# ETH_IFC.net
KiCad netlist of a schematic drawn in Altium Designer
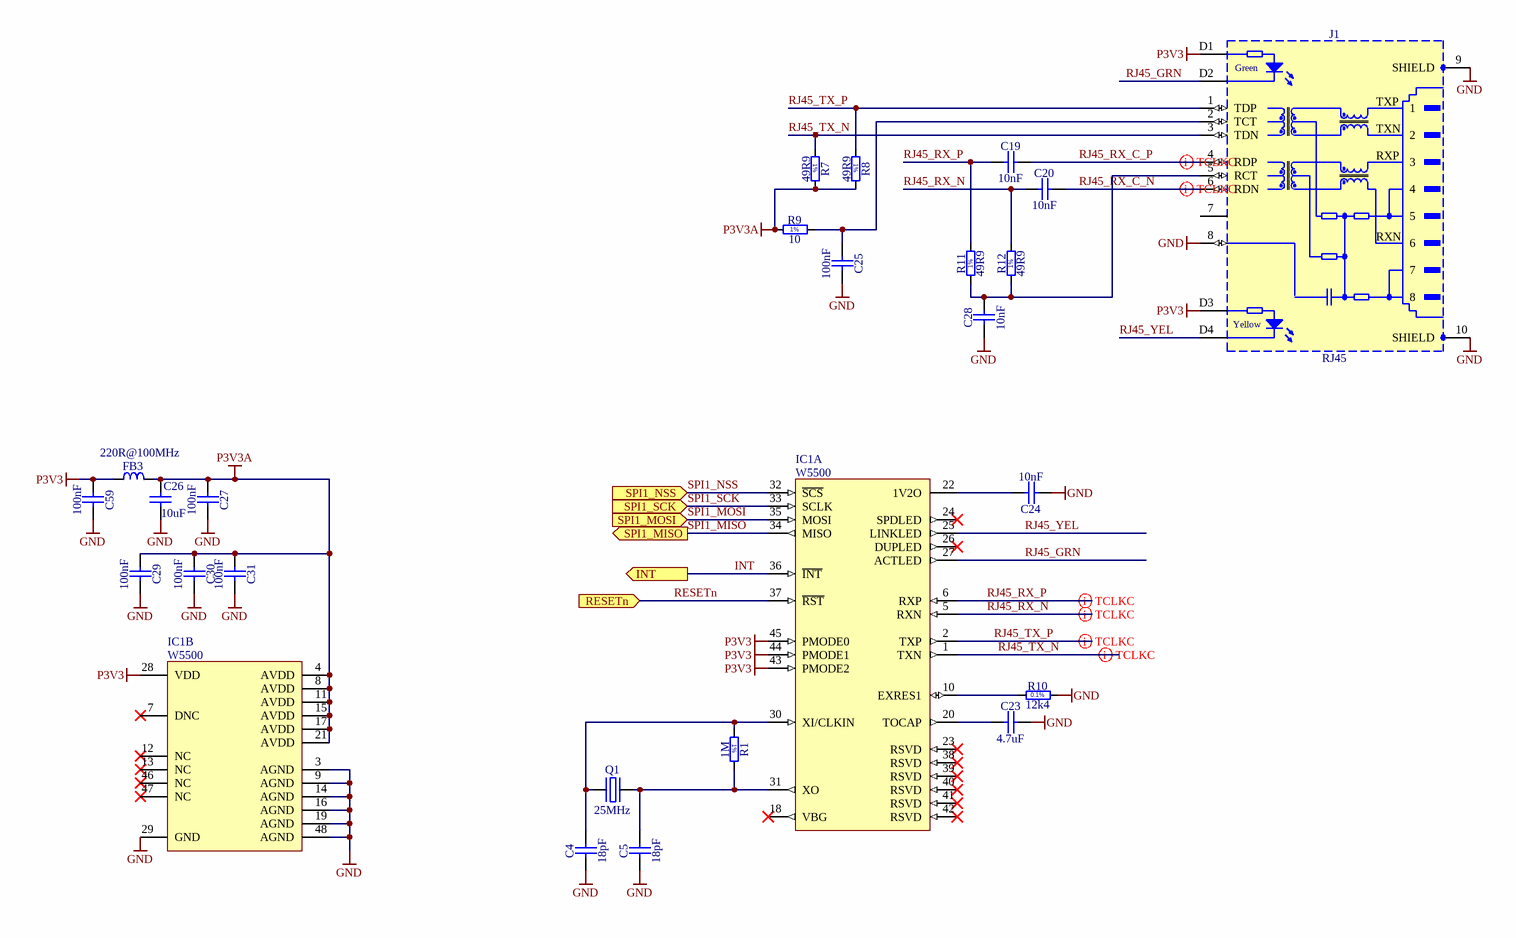
[diagram p0: ETH_IFC.SchDoc]

(export (version "E")
  (design (tool "Eeschema 10.0.6"))
  (components
    (comp (ref "C4")
      (value "18pF")
      (footprint "CAPC1005X55N")
      (description "Non-polarised capacitor")
      (fields
        (field (name "PART NUMBER") "CC0402_18PF_50V_5%_C0G")
        (field (name "VOLTAGE") "50V")
        (field (name "AUTHOR") "CERN DEM JLC")
      )
      (libsource (lib "Capacitors") (part "Capacitor - non polarized"))
    )
    (comp (ref "C5")
      (value "18pF")
      (footprint "CAPC1005X55N")
      (description "Non-polarised capacitor")
      (fields
        (field (name "PART NUMBER") "CC0402_18PF_50V_5%_C0G")
        (field (name "VOLTAGE") "50V")
        (field (name "AUTHOR") "CERN DEM JLC")
      )
      (libsource (lib "Capacitors") (part "Capacitor - non polarized"))
    )
    (comp (ref "C19")
      (value "10nF")
      (footprint "CAPC1608X87N")
      (description "Non-polarised capacitor")
      (fields
        (field (name "PART NUMBER") "CC0603_10NF_50V_5%_C0G")
        (field (name "VOLTAGE") "50V")
        (field (name "AUTHOR") "CERN DEM JLC")
      )
      (libsource (lib "Capacitors") (part "Capacitor - non polarized"))
    )
    (comp (ref "C20")
      (value "10nF")
      (footprint "CAPC1608X87N")
      (description "Non-polarised capacitor")
      (fields
        (field (name "PART NUMBER") "CC0603_10NF_50V_5%_C0G")
        (field (name "VOLTAGE") "50V")
        (field (name "AUTHOR") "CERN DEM JLC")
      )
      (libsource (lib "Capacitors") (part "Capacitor - non polarized"))
    )
    (comp (ref "C23")
      (value "4.7uF")
      (footprint "CAPC1709X95N")
      (description "Non-polarised capacitor")
      (fields
        (field (name "PART NUMBER") "CC0603_4.7UF_16V_10%_X5R")
        (field (name "VOLTAGE") "16V")
        (field (name "AUTHOR") "CERN DEM JLC")
      )
      (libsource (lib "Capacitors") (part "Capacitor - non polarized"))
    )
    (comp (ref "C24")
      (value "10nF")
      (footprint "CAPC1608X87N")
      (description "Non-polarised capacitor")
      (fields
        (field (name "PART NUMBER") "CC0603_10NF_50V_5%_C0G")
        (field (name "VOLTAGE") "50V")
        (field (name "AUTHOR") "CERN DEM JLC")
      )
      (libsource (lib "Capacitors") (part "Capacitor - non polarized"))
    )
    (comp (ref "C25")
      (value "100nF")
      (footprint "CAPC1005X55N")
      (description "Non-polarised capacitor")
      (fields
        (field (name "PART NUMBER") "CC0402_100NF_16V_10%_X7R")
        (field (name "VOLTAGE") "16V")
        (field (name "AUTHOR") "CERN DEM JLC")
      )
      (libsource (lib "Capacitors") (part "Capacitor - non polarized"))
    )
    (comp (ref "C26")
      (value "10uF")
      (footprint "CAPC2012X135N")
      (description "Non-polarised capacitor")
      (fields
        (field (name "PART NUMBER") "CC0805_10UF_10V_10%_X7R")
        (field (name "VOLTAGE") "10V")
        (field (name "AUTHOR") "CERN DEM JLC")
      )
      (libsource (lib "Capacitors") (part "Capacitor - non polarized"))
    )
    (comp (ref "C27")
      (value "100nF")
      (footprint "CAPC1005X55N")
      (description "Non-polarised capacitor")
      (fields
        (field (name "PART NUMBER") "CC0402_100NF_16V_10%_X7R")
        (field (name "VOLTAGE") "16V")
        (field (name "AUTHOR") "CERN DEM JLC")
      )
      (libsource (lib "Capacitors") (part "Capacitor - non polarized"))
    )
    (comp (ref "C28")
      (value "10nF")
      (footprint "CAPC1608X87N")
      (description "Non-polarised capacitor")
      (fields
        (field (name "PART NUMBER") "CC0603_10NF_50V_5%_C0G")
        (field (name "VOLTAGE") "50V")
        (field (name "AUTHOR") "CERN DEM JLC")
      )
      (libsource (lib "Capacitors") (part "Capacitor - non polarized"))
    )
    (comp (ref "C29")
      (value "100nF")
      (footprint "CAPC1005X55N")
      (description "Non-polarised capacitor")
      (fields
        (field (name "PART NUMBER") "CC0402_100NF_16V_10%_X7R")
        (field (name "VOLTAGE") "16V")
        (field (name "AUTHOR") "CERN DEM JLC")
      )
      (libsource (lib "Capacitors") (part "Capacitor - non polarized"))
    )
    (comp (ref "C30")
      (value "100nF")
      (footprint "CAPC1005X55N")
      (description "Non-polarised capacitor")
      (fields
        (field (name "PART NUMBER") "CC0402_100NF_16V_10%_X7R")
        (field (name "VOLTAGE") "16V")
        (field (name "AUTHOR") "CERN DEM JLC")
      )
      (libsource (lib "Capacitors") (part "Capacitor - non polarized"))
    )
    (comp (ref "C31")
      (value "100nF")
      (footprint "CAPC1005X55N")
      (description "Non-polarised capacitor")
      (fields
        (field (name "PART NUMBER") "CC0402_100NF_16V_10%_X7R")
        (field (name "VOLTAGE") "16V")
        (field (name "AUTHOR") "CERN DEM JLC")
      )
      (libsource (lib "Capacitors") (part "Capacitor - non polarized"))
    )
    (comp (ref "C59")
      (value "100nF")
      (footprint "CAPC1005X55N")
      (description "Non-polarised capacitor")
      (fields
        (field (name "PART NUMBER") "CC0402_100NF_16V_10%_X7R")
        (field (name "VOLTAGE") "16V")
        (field (name "AUTHOR") "CERN DEM JLC")
      )
      (libsource (lib "Capacitors") (part "Capacitor - non polarized"))
    )
    (comp (ref "FB3")
      (value "220R@100MHz")
      (footprint "INDC2012X105N")
      (description "Inductor")
      (fields
        (field (name "PART NUMBER") "IND0805_MURATA_BLM21PG221SN1D")
        (field (name "POWER") "2A")
        (field (name "AUTHOR") "CERN DEM JLC")
      )
      (libsource (lib "Inductors & Transformers") (part "Inductor"))
    )
    (comp (ref "IC1")
      (value "W5500")
      (footprint "QFP50P900X900X160-48N")
      (description "iEthernet W5500 TCP/IP Performance and High Speed SPI Ethernet Controller")
      (fields (field (name "MANUFACTURER") "WIZNET") (field (name "AUTHOR") "CERN DEM MR"))
      (libsource (lib "ICs And Semiconductors") (part "W5500"))
    )
    (comp (ref "J1")
      (value "RJ45")
      (footprint "TYCO_5-6605308-1")
      (fields
        (field (name "PART NUMBER") "TYCO_5-6605308-1")
        (field (name "MANUFACTURER") "TYCO ELECTRONICS")
        (field (name "MANUFACTURER PART NUMBER") "5-6605308-1")
        (field (name "AUTHOR") "CERN DEM JLC")
      )
      (libsource (lib "Connectors") (part "TYCO_5-6605308-1"))
    )
    (comp (ref "Q1")
      (value "25MHz")
      (footprint "XTAL_TXC_AA")
      (description "Quartz Crystal")
      (fields
        (field (name "PART NUMBER") "XTAL_25MHZ_TXC_AA-25.000MALE-T")
        (field (name "MANUFACTURER") "TXC CORPORATION")
        (field (name "AUTHOR") "GK")
      )
      (libsource (lib "Crystals_Oscillators") (part "XTAL_25MHZ_TXC_AA-25.000MALE-T"))
    )
    (comp (ref "R1")
      (value "1M")
      (footprint "RESC1005X40N")
      (description "Resistor - 1%")
      (fields
        (field (name "PART NUMBER") "R0402_1M_1%_0.0625W_100PPM")
        (field (name "POWER") "0.0625W")
        (field (name "AUTHOR") "CERN DEM JLC")
      )
      (libsource (lib "Resistors") (part "Resistor - 1%"))
    )
    (comp (ref "R7")
      (value "49R9")
      (footprint "RESC1005X40N")
      (description "Resistor - 1%")
      (fields
        (field (name "PART NUMBER") "R0402_49R9_1%_0.0625W_100PPM")
        (field (name "POWER") "0.0625W")
        (field (name "AUTHOR") "CERN DEM JLC")
      )
      (libsource (lib "Resistors") (part "Resistor - 1%"))
    )
    (comp (ref "R8")
      (value "49R9")
      (footprint "RESC1005X40N")
      (description "Resistor - 1%")
      (fields
        (field (name "PART NUMBER") "R0402_49R9_1%_0.0625W_100PPM")
        (field (name "POWER") "0.0625W")
        (field (name "AUTHOR") "CERN DEM JLC")
      )
      (libsource (lib "Resistors") (part "Resistor - 1%"))
    )
    (comp (ref "R9")
      (value "10")
      (footprint "RESC1005X40N")
      (description "Resistor - 1%")
      (fields
        (field (name "PART NUMBER") "R0402_10R_1%_0.0625W_200PPM")
        (field (name "POWER") "0.0625W")
        (field (name "AUTHOR") "CERN DEM JLC")
      )
      (libsource (lib "Resistors") (part "Resistor - 1%"))
    )
    (comp (ref "R10")
      (value "12k4")
      (footprint "RESC1608X55N")
      (description "Resistor - 0.1%")
      (fields
        (field (name "PART NUMBER") "R0603_12K4_0.1%_0.063W_10PPM")
        (field (name "POWER") "0.063W")
        (field (name "AUTHOR") "CERN DEM JLC")
      )
      (libsource (lib "Resistors") (part "Resistor - 0.1%"))
    )
    (comp (ref "R11")
      (value "49R9")
      (footprint "RESC1005X40N")
      (description "Resistor - 1%")
      (fields
        (field (name "PART NUMBER") "R0402_49R9_1%_0.0625W_100PPM")
        (field (name "POWER") "0.0625W")
        (field (name "AUTHOR") "CERN DEM JLC")
      )
      (libsource (lib "Resistors") (part "Resistor - 1%"))
    )
    (comp (ref "R12")
      (value "49R9")
      (footprint "RESC1005X40N")
      (description "Resistor - 1%")
      (fields
        (field (name "PART NUMBER") "R0402_49R9_1%_0.0625W_100PPM")
        (field (name "POWER") "0.0625W")
        (field (name "AUTHOR") "CERN DEM JLC")
      )
      (libsource (lib "Resistors") (part "Resistor - 1%"))
    )
  )
  (nets
    (net (code "1") (name "/INT") (class "Default")
      (node (ref "IC1") (pin "36") (pinfunction "~{INT}_36") (pintype "input"))
    )
    (net (code "2") (name "/RESETn") (class "Default")
      (node (ref "IC1") (pin "37") (pinfunction "~{RST}_37") (pintype "input"))
    )
    (net (code "3") (name "/RJ45_GRN") (class "Default")
      (node (ref "IC1") (pin "27") (pinfunction "ACTLED_27") (pintype "output"))
      (node (ref "J1") (pin "D2") (pinfunction "D2_D2") (pintype "passive"))
    )
    (net (code "4") (name "/RJ45_RX_C_N") (class "Default")
      (node (ref "C20") (pin "2") (pinfunction "2_2") (pintype "passive"))
      (node (ref "J1") (pin "6") (pinfunction "RDN_6") (pintype "bidirectional"))
    )
    (net (code "5") (name "/RJ45_RX_C_P") (class "Default")
      (node (ref "C19") (pin "2") (pinfunction "2_2") (pintype "passive"))
      (node (ref "J1") (pin "4") (pinfunction "RDP_4") (pintype "bidirectional"))
    )
    (net (code "6") (name "/RJ45_RX_N") (class "Default")
      (node (ref "C20") (pin "1") (pinfunction "1_1") (pintype "passive"))
      (node (ref "IC1") (pin "5") (pinfunction "RXN_5") (pintype "input"))
      (node (ref "R12") (pin "2") (pinfunction "2_2") (pintype "passive"))
    )
    (net (code "7") (name "/RJ45_RX_P") (class "Default")
      (node (ref "C19") (pin "1") (pinfunction "1_1") (pintype "passive"))
      (node (ref "IC1") (pin "6") (pinfunction "RXP_6") (pintype "input"))
      (node (ref "R11") (pin "2") (pinfunction "2_2") (pintype "passive"))
    )
    (net (code "8") (name "/RJ45_TX_N") (class "Default")
      (node (ref "IC1") (pin "1") (pinfunction "TXN_1") (pintype "output"))
      (node (ref "J1") (pin "3") (pinfunction "TDN_3") (pintype "bidirectional"))
      (node (ref "R7") (pin "1") (pinfunction "1_1") (pintype "passive"))
    )
    (net (code "9") (name "/RJ45_TX_P") (class "Default")
      (node (ref "IC1") (pin "2") (pinfunction "TXP_2") (pintype "output"))
      (node (ref "J1") (pin "1") (pinfunction "TDP_1") (pintype "bidirectional"))
      (node (ref "R8") (pin "1") (pinfunction "1_1") (pintype "passive"))
    )
    (net (code "10") (name "/RJ45_YEL") (class "Default")
      (node (ref "IC1") (pin "25") (pinfunction "LINKLED_25") (pintype "output"))
      (node (ref "J1") (pin "D4") (pinfunction "D4_D4") (pintype "passive"))
    )
    (net (code "11") (name "/SPI1_MISO") (class "Default")
      (node (ref "IC1") (pin "34") (pinfunction "MISO_34") (pintype "output"))
    )
    (net (code "12") (name "/SPI1_MOSI") (class "Default")
      (node (ref "IC1") (pin "35") (pinfunction "MOSI_35") (pintype "input"))
    )
    (net (code "13") (name "/SPI1_NSS") (class "Default")
      (node (ref "IC1") (pin "32") (pinfunction "~{SCS}_32") (pintype "input"))
    )
    (net (code "14") (name "/SPI1_SCK") (class "Default")
      (node (ref "IC1") (pin "33") (pinfunction "SCLK_33") (pintype "input"))
    )
    (net (code "15") (name "GND") (class "Default")
      (node (ref "C23") (pin "2") (pinfunction "2_2") (pintype "passive"))
      (node (ref "C24") (pin "1") (pinfunction "1_1") (pintype "passive"))
      (node (ref "C25") (pin "2") (pinfunction "2_2") (pintype "passive"))
      (node (ref "C26") (pin "2") (pinfunction "2_2") (pintype "passive"))
      (node (ref "C27") (pin "2") (pinfunction "2_2") (pintype "passive"))
      (node (ref "C28") (pin "1") (pinfunction "1_1") (pintype "passive"))
      (node (ref "C29") (pin "2") (pinfunction "2_2") (pintype "passive"))
      (node (ref "C30") (pin "2") (pinfunction "2_2") (pintype "passive"))
      (node (ref "C31") (pin "2") (pinfunction "2_2") (pintype "passive"))
      (node (ref "C4") (pin "1") (pinfunction "1_1") (pintype "passive"))
      (node (ref "C5") (pin "1") (pinfunction "1_1") (pintype "passive"))
      (node (ref "C59") (pin "2") (pinfunction "2_2") (pintype "passive"))
      (node (ref "IC1") (pin "14") (pinfunction "AGND_14") (pintype "power_in"))
      (node (ref "IC1") (pin "16") (pinfunction "AGND_16") (pintype "power_in"))
      (node (ref "IC1") (pin "19") (pinfunction "AGND_19") (pintype "power_in"))
      (node (ref "IC1") (pin "29") (pinfunction "GND_29") (pintype "power_in"))
      (node (ref "IC1") (pin "3") (pinfunction "AGND_3") (pintype "power_in"))
      (node (ref "IC1") (pin "48") (pinfunction "AGND_48") (pintype "power_in"))
      (node (ref "IC1") (pin "9") (pinfunction "AGND_9") (pintype "power_in"))
      (node (ref "J1") (pin "10") (pinfunction "SHIELD_10") (pintype "power_in"))
      (node (ref "J1") (pin "8") (pinfunction "8_8") (pintype "bidirectional"))
      (node (ref "J1") (pin "9") (pinfunction "SHIELD_9") (pintype "power_in"))
      (node (ref "R10") (pin "2") (pinfunction "2_2") (pintype "passive"))
    )
    (net (code "16") (name "Net-(IC1A-1V2O)") (class "Default")
      (node (ref "C24") (pin "2") (pinfunction "2_2") (pintype "passive"))
      (node (ref "IC1") (pin "22") (pinfunction "1V2O_22") (pintype "power_in"))
    )
    (net (code "17") (name "Net-(IC1A-EXRES1)") (class "Default")
      (node (ref "IC1") (pin "10") (pinfunction "EXRES1_10") (pintype "bidirectional"))
      (node (ref "R10") (pin "1") (pinfunction "1_1") (pintype "passive"))
    )
    (net (code "18") (name "Net-(IC1A-TOCAP)") (class "Default")
      (node (ref "C23") (pin "1") (pinfunction "1_1") (pintype "passive"))
      (node (ref "IC1") (pin "20") (pinfunction "TOCAP_20") (pintype "output"))
    )
    (net (code "19") (name "Net-(IC1A-XI{slash}CLKIN)") (class "Default")
      (node (ref "C4") (pin "2") (pinfunction "2_2") (pintype "passive"))
      (node (ref "IC1") (pin "30") (pinfunction "XI/CLKIN_30") (pintype "input"))
      (node (ref "Q1") (pin "1") (pinfunction "OSC1_1") (pintype "passive"))
      (node (ref "R1") (pin "1") (pinfunction "1_1") (pintype "passive"))
    )
    (net (code "20") (name "Net-(IC1A-XO)") (class "Default")
      (node (ref "C5") (pin "2") (pinfunction "2_2") (pintype "passive"))
      (node (ref "IC1") (pin "31") (pinfunction "XO_31") (pintype "output"))
      (node (ref "Q1") (pin "2") (pinfunction "OSC2_2") (pintype "passive"))
      (node (ref "R1") (pin "2") (pinfunction "2_2") (pintype "passive"))
    )
    (net (code "21") (name "Net-(J1-RCT)") (class "Default")
      (node (ref "C28") (pin "2") (pinfunction "2_2") (pintype "passive"))
      (node (ref "J1") (pin "5") (pinfunction "RCT_5") (pintype "bidirectional"))
      (node (ref "R11") (pin "1") (pinfunction "1_1") (pintype "passive"))
      (node (ref "R12") (pin "1") (pinfunction "1_1") (pintype "passive"))
    )
    (net (code "22") (name "Net-(J1-TCT)") (class "Default")
      (node (ref "C25") (pin "1") (pinfunction "1_1") (pintype "passive"))
      (node (ref "J1") (pin "2") (pinfunction "TCT_2") (pintype "bidirectional"))
      (node (ref "R9") (pin "2") (pinfunction "2_2") (pintype "passive"))
    )
    (net (code "23") (name "P3V3") (class "Default")
      (node (ref "C59") (pin "1") (pinfunction "1_1") (pintype "passive"))
      (node (ref "FB3") (pin "1") (pinfunction "1_1") (pintype "passive"))
      (node (ref "IC1") (pin "28") (pinfunction "VDD_28") (pintype "power_in"))
      (node (ref "IC1") (pin "43") (pinfunction "PMODE2_43") (pintype "input"))
      (node (ref "IC1") (pin "44") (pinfunction "PMODE1_44") (pintype "input"))
      (node (ref "IC1") (pin "45") (pinfunction "PMODE0_45") (pintype "input"))
      (node (ref "J1") (pin "D1") (pinfunction "D1_D1") (pintype "passive"))
      (node (ref "J1") (pin "D3") (pinfunction "D3_D3") (pintype "passive"))
    )
    (net (code "24") (name "P3V3A") (class "Default")
      (node (ref "C26") (pin "1") (pinfunction "1_1") (pintype "passive"))
      (node (ref "C27") (pin "1") (pinfunction "1_1") (pintype "passive"))
      (node (ref "C29") (pin "1") (pinfunction "1_1") (pintype "passive"))
      (node (ref "C30") (pin "1") (pinfunction "1_1") (pintype "passive"))
      (node (ref "C31") (pin "1") (pinfunction "1_1") (pintype "passive"))
      (node (ref "FB3") (pin "2") (pinfunction "2_2") (pintype "passive"))
      (node (ref "IC1") (pin "11") (pinfunction "AVDD_11") (pintype "power_in"))
      (node (ref "IC1") (pin "15") (pinfunction "AVDD_15") (pintype "power_in"))
      (node (ref "IC1") (pin "17") (pinfunction "AVDD_17") (pintype "power_in"))
      (node (ref "IC1") (pin "21") (pinfunction "AVDD_21") (pintype "power_in"))
      (node (ref "IC1") (pin "4") (pinfunction "AVDD_4") (pintype "power_in"))
      (node (ref "IC1") (pin "8") (pinfunction "AVDD_8") (pintype "power_in"))
      (node (ref "R7") (pin "2") (pinfunction "2_2") (pintype "passive"))
      (node (ref "R8") (pin "2") (pinfunction "2_2") (pintype "passive"))
      (node (ref "R9") (pin "1") (pinfunction "1_1") (pintype "passive"))
    )
    (net (code "25") (name "unconnected-(IC1A-DUPLED-Pad26)") (class "Default")
      (node (ref "IC1") (pin "26") (pinfunction "DUPLED_26") (pintype "output+no_connect"))
    )
    (net (code "26") (name "unconnected-(IC1A-RSVD-Pad23)") (class "Default")
      (node (ref "IC1") (pin "23") (pinfunction "RSVD_23") (pintype "input+no_connect"))
    )
    (net (code "27") (name "unconnected-(IC1A-RSVD-Pad38)") (class "Default")
      (node (ref "IC1") (pin "38") (pinfunction "RSVD_38") (pintype "input+no_connect"))
    )
    (net (code "28") (name "unconnected-(IC1A-RSVD-Pad39)") (class "Default")
      (node (ref "IC1") (pin "39") (pinfunction "RSVD_39") (pintype "input+no_connect"))
    )
    (net (code "29") (name "unconnected-(IC1A-RSVD-Pad40)") (class "Default")
      (node (ref "IC1") (pin "40") (pinfunction "RSVD_40") (pintype "input+no_connect"))
    )
    (net (code "30") (name "unconnected-(IC1A-RSVD-Pad41)") (class "Default")
      (node (ref "IC1") (pin "41") (pinfunction "RSVD_41") (pintype "input+no_connect"))
    )
    (net (code "31") (name "unconnected-(IC1A-RSVD-Pad42)") (class "Default")
      (node (ref "IC1") (pin "42") (pinfunction "RSVD_42") (pintype "input+no_connect"))
    )
    (net (code "32") (name "unconnected-(IC1A-SPDLED-Pad24)") (class "Default")
      (node (ref "IC1") (pin "24") (pinfunction "SPDLED_24") (pintype "output+no_connect"))
    )
    (net (code "33") (name "unconnected-(IC1A-VBG-Pad18)") (class "Default")
      (node (ref "IC1") (pin "18") (pinfunction "VBG_18") (pintype "output+no_connect"))
    )
    (net (code "34") (name "unconnected-(IC1B-DNC-Pad7)") (class "Default")
      (node (ref "IC1") (pin "7") (pinfunction "DNC_7") (pintype "passive+no_connect"))
    )
    (net (code "35") (name "unconnected-(IC1B-NC-Pad12)") (class "Default")
      (node (ref "IC1") (pin "12") (pinfunction "NC_12") (pintype "passive+no_connect"))
    )
    (net (code "36") (name "unconnected-(IC1B-NC-Pad13)") (class "Default")
      (node (ref "IC1") (pin "13") (pinfunction "NC_13") (pintype "passive+no_connect"))
    )
    (net (code "37") (name "unconnected-(IC1B-NC-Pad46)") (class "Default")
      (node (ref "IC1") (pin "46") (pinfunction "NC_46") (pintype "passive+no_connect"))
    )
    (net (code "38") (name "unconnected-(IC1B-NC-Pad47)") (class "Default")
      (node (ref "IC1") (pin "47") (pinfunction "NC_47") (pintype "passive+no_connect"))
    )
    (net (code "39") (name "unconnected-(J1-Pad7)") (class "Default")
      (node (ref "J1") (pin "7") (pinfunction "7_7") (pintype "passive"))
    )
  )
)
